# Sheet1.net
KiCad netlist of a schematic drawn in Altium Designer
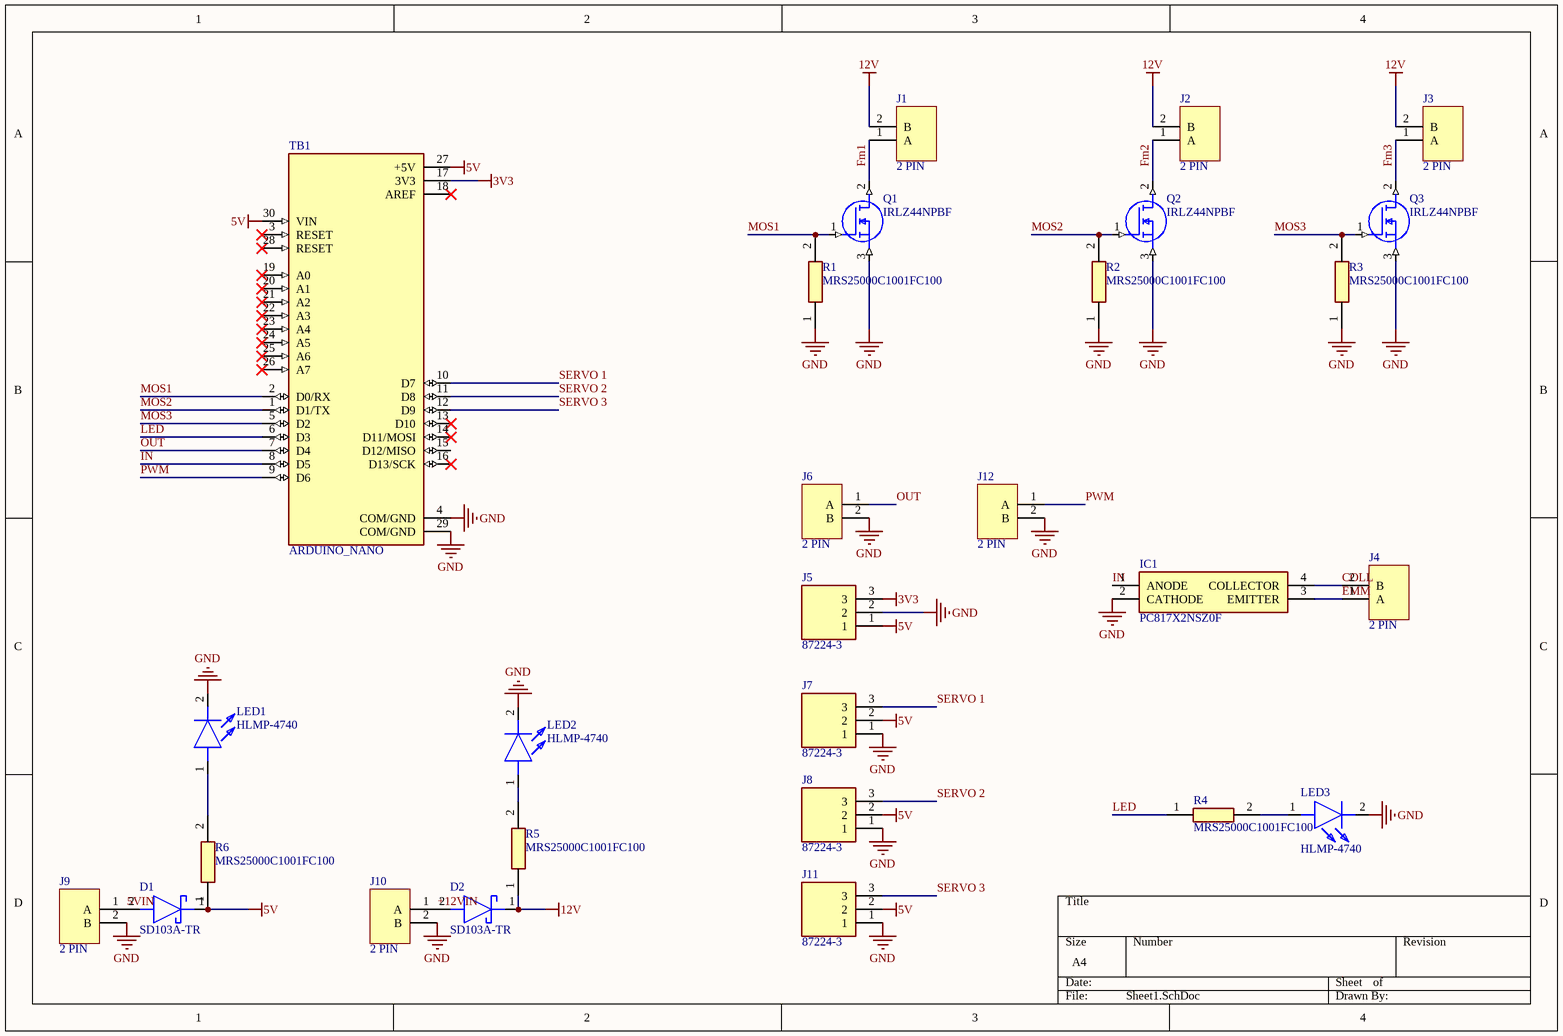
[diagram p0: Sheet1.SchDoc]

(export (version "E")
  (design (tool "Eeschema 10.0.6"))
  (components
    (comp (ref "D1")
      (value "SD103A-TR")
      (footprint "SamacSys:DIOAD950W60L350D150")
      (description "Schottky Diode")
      (fields (field (name "MOUSER PART NUMBER") "625-SD103A"))
      (libsource (lib "SamacSys") (part "SD103A-TR"))
    )
    (comp (ref "D2")
      (value "SD103A-TR")
      (footprint "SamacSys:DIOAD950W60L350D150")
      (description "Schottky Diode")
      (fields (field (name "MOUSER PART NUMBER") "625-SD103A"))
      (libsource (lib "SamacSys") (part "SD103A-TR"))
    )
    (comp (ref "IC1")
      (value "PC817X2NSZ0F")
      (footprint "SamacSys:DIP762W60P254L458H400Q4N")
      (description "Integrated Circuit")
      (libsource (lib "SamacSys") (part "PC817X2NSZ0F"))
    )
    (comp (ref "J1")
      (value "2 PIN")
      (footprint "Header 2_PIN")
      (libsource (lib "") (part "Connector_2Pin_1"))
    )
    (comp (ref "J2")
      (value "2 PIN")
      (footprint "Header 2_PIN")
      (libsource (lib "") (part "Connector_2Pin_1"))
    )
    (comp (ref "J3")
      (value "2 PIN")
      (footprint "Header 2_PIN")
      (libsource (lib "") (part "Connector_2Pin_1"))
    )
    (comp (ref "J4")
      (value "2 PIN")
      (footprint "Header 2_PIN")
      (libsource (lib "") (part "Connector_2Pin_1"))
    )
    (comp (ref "J5")
      (value "87224-3")
      (footprint "SamacSys:872243")
      (description "Connector")
      (fields (field (name "MOUSER PART NUMBER") "571-872243"))
      (libsource (lib "SamacSys") (part "87224-3"))
    )
    (comp (ref "J6")
      (value "2 PIN")
      (footprint "Header 2_PIN")
      (libsource (lib "Custom_Component") (part "Connector_2Pin"))
    )
    (comp (ref "J7")
      (value "87224-3")
      (footprint "SamacSys:872243")
      (description "Connector")
      (fields (field (name "MOUSER PART NUMBER") "571-872243"))
      (libsource (lib "SamacSys") (part "87224-3"))
    )
    (comp (ref "J8")
      (value "87224-3")
      (footprint "SamacSys:872243")
      (description "Connector")
      (fields (field (name "MOUSER PART NUMBER") "571-872243"))
      (libsource (lib "SamacSys") (part "87224-3"))
    )
    (comp (ref "J9")
      (value "2 PIN")
      (footprint "Header 2_PIN")
      (libsource (lib "Custom_Component") (part "Connector_2Pin"))
    )
    (comp (ref "J10")
      (value "2 PIN")
      (footprint "Header 2_PIN")
      (libsource (lib "Custom_Component") (part "Connector_2Pin"))
    )
    (comp (ref "J11")
      (value "87224-3")
      (footprint "SamacSys:872243")
      (description "Connector")
      (fields (field (name "MOUSER PART NUMBER") "571-872243"))
      (libsource (lib "SamacSys") (part "87224-3"))
    )
    (comp (ref "J12")
      (value "2 PIN")
      (footprint "Header 2_PIN")
      (libsource (lib "Custom_Component") (part "Connector_2Pin"))
    )
    (comp (ref "LED1")
      (value "HLMP-4740")
      (footprint "SamacSys:HLMP4740")
      (description "LED")
      (fields (field (name "MOUSER PART NUMBER") "630-HLMP-4740"))
      (libsource (lib "SamacSys") (part "HLMP-4740"))
    )
    (comp (ref "LED2")
      (value "HLMP-4740")
      (footprint "SamacSys:HLMP4740")
      (description "LED")
      (fields (field (name "MOUSER PART NUMBER") "630-HLMP-4740"))
      (libsource (lib "SamacSys") (part "HLMP-4740"))
    )
    (comp (ref "LED3")
      (value "HLMP-4740")
      (footprint "SamacSys:HLMP4740")
      (description "LED")
      (fields (field (name "MOUSER PART NUMBER") "630-HLMP-4740"))
      (libsource (lib "SamacSys") (part "HLMP-4740"))
    )
    (comp (ref "Q1")
      (value "IRLZ44NPBF")
      (footprint "SamacSys:TO254P469X1042X1967-3P")
      (description "MOSFET (N-Channel)")
      (fields (field (name "MOUSER PART NUMBER") "942-IRLZ44NPBF"))
      (libsource (lib "*") (part "IRLZ44NPBF"))
    )
    (comp (ref "Q2")
      (value "IRLZ44NPBF")
      (footprint "SamacSys:TO254P469X1042X1967-3P")
      (description "MOSFET (N-Channel)")
      (fields (field (name "MOUSER PART NUMBER") "942-IRLZ44NPBF"))
      (libsource (lib "*") (part "IRLZ44NPBF"))
    )
    (comp (ref "Q3")
      (value "IRLZ44NPBF")
      (footprint "SamacSys:TO254P469X1042X1967-3P")
      (description "MOSFET (N-Channel)")
      (fields (field (name "MOUSER PART NUMBER") "942-IRLZ44NPBF"))
      (libsource (lib "*") (part "IRLZ44NPBF"))
    )
    (comp (ref "R1")
      (value "MRS25000C1001FC100")
      (footprint "SamacSys:RESAD1650W60L650D250")
      (description "Resistor")
      (fields (field (name "MOUSER PART NUMBER") "594-MRS25000C1001FC1"))
      (libsource (lib "SamacSys") (part "MRS25000C1001FC100"))
    )
    (comp (ref "R2")
      (value "MRS25000C1001FC100")
      (footprint "SamacSys:RESAD1650W60L650D250")
      (description "Resistor")
      (fields (field (name "MOUSER PART NUMBER") "594-MRS25000C1001FC1"))
      (libsource (lib "SamacSys") (part "MRS25000C1001FC100"))
    )
    (comp (ref "R3")
      (value "MRS25000C1001FC100")
      (footprint "SamacSys:RESAD1650W60L650D250")
      (description "Resistor")
      (fields (field (name "MOUSER PART NUMBER") "594-MRS25000C1001FC1"))
      (libsource (lib "SamacSys") (part "MRS25000C1001FC100"))
    )
    (comp (ref "R4")
      (value "MRS25000C1001FC100")
      (footprint "SamacSys:RESAD1650W60L650D250")
      (description "Resistor")
      (fields (field (name "MOUSER PART NUMBER") "594-MRS25000C1001FC1"))
      (libsource (lib "") (part "MRS25000C1001FC100_1"))
    )
    (comp (ref "R5")
      (value "MRS25000C1001FC100")
      (footprint "SamacSys:RESAD1650W60L650D250")
      (description "Resistor")
      (fields (field (name "MOUSER PART NUMBER") "594-MRS25000C1001FC1"))
      (libsource (lib "SamacSys") (part "MRS25000C1001FC100"))
    )
    (comp (ref "R6")
      (value "MRS25000C1001FC100")
      (footprint "SamacSys:RESAD1650W60L650D250")
      (description "Resistor")
      (fields (field (name "MOUSER PART NUMBER") "594-MRS25000C1001FC1"))
      (libsource (lib "SamacSys") (part "MRS25000C1001FC100"))
    )
    (comp (ref "TB1")
      (value "ARDUINO_NANO")
      (footprint "SHIELD_ARDUINO_NANO")
      (description "Small, complete, and breadboard-friendly board based on the ATmega328 (Arduino Nano 3.x)")
      (fields (field (name "MP") "Arduino Nano") (field (name "MF") "Arduino"))
      (libsource (lib "ARDUINO_NANO") (part "ARDUINO_NANO"))
    )
  )
  (nets
    (net (code "1") (name "/+12VIN") (class "Default")
      (node (ref "D2") (pin "2") (pinfunction "A_2") (pintype "passive"))
      (node (ref "J10") (pin "1") (pinfunction "A_1") (pintype "passive"))
    )
    (net (code "2") (name "/5VIN") (class "Default")
      (node (ref "D1") (pin "2") (pinfunction "A_2") (pintype "passive"))
      (node (ref "J9") (pin "1") (pinfunction "A_1") (pintype "passive"))
    )
    (net (code "3") (name "/COLL") (class "Default")
      (node (ref "IC1") (pin "4") (pinfunction "COLLECTOR_4") (pintype "passive"))
      (node (ref "J4") (pin "2") (pinfunction "B_2") (pintype "passive"))
    )
    (net (code "4") (name "/EMM") (class "Default")
      (node (ref "IC1") (pin "3") (pinfunction "EMITTER_3") (pintype "passive"))
      (node (ref "J4") (pin "1") (pinfunction "A_1") (pintype "passive"))
    )
    (net (code "5") (name "/Fm1") (class "Default")
      (node (ref "J1") (pin "1") (pinfunction "A_1") (pintype "passive"))
      (node (ref "Q1") (pin "2") (pinfunction "D_2") (pintype "output"))
    )
    (net (code "6") (name "/Fm2") (class "Default")
      (node (ref "J2") (pin "1") (pinfunction "A_1") (pintype "passive"))
      (node (ref "Q2") (pin "2") (pinfunction "D_2") (pintype "output"))
    )
    (net (code "7") (name "/Fm3") (class "Default")
      (node (ref "J3") (pin "1") (pinfunction "A_1") (pintype "passive"))
      (node (ref "Q3") (pin "2") (pinfunction "D_2") (pintype "output"))
    )
    (net (code "8") (name "/IN") (class "Default")
      (node (ref "IC1") (pin "1") (pinfunction "ANODE_1") (pintype "passive"))
      (node (ref "TB1") (pin "8") (pinfunction "D5_8") (pintype "bidirectional"))
    )
    (net (code "9") (name "/LED") (class "Default")
      (node (ref "R4") (pin "1") (pinfunction "1_1") (pintype "passive"))
      (node (ref "TB1") (pin "6") (pinfunction "D3_6") (pintype "bidirectional"))
    )
    (net (code "10") (name "/MOS1") (class "Default")
      (node (ref "Q1") (pin "1") (pinfunction "G_1") (pintype "input"))
      (node (ref "R1") (pin "2") (pinfunction "2_2") (pintype "passive"))
      (node (ref "TB1") (pin "2") (pinfunction "D0/RX_2") (pintype "bidirectional"))
    )
    (net (code "11") (name "/MOS2") (class "Default")
      (node (ref "Q2") (pin "1") (pinfunction "G_1") (pintype "input"))
      (node (ref "R2") (pin "2") (pinfunction "2_2") (pintype "passive"))
      (node (ref "TB1") (pin "1") (pinfunction "D1/TX_1") (pintype "bidirectional"))
    )
    (net (code "12") (name "/MOS3") (class "Default")
      (node (ref "Q3") (pin "1") (pinfunction "G_1") (pintype "input"))
      (node (ref "R3") (pin "2") (pinfunction "2_2") (pintype "passive"))
      (node (ref "TB1") (pin "5") (pinfunction "D2_5") (pintype "bidirectional"))
    )
    (net (code "13") (name "/OUT") (class "Default")
      (node (ref "J6") (pin "1") (pinfunction "A_1") (pintype "passive"))
      (node (ref "TB1") (pin "7") (pinfunction "D4_7") (pintype "bidirectional"))
    )
    (net (code "14") (name "/PWM") (class "Default")
      (node (ref "J12") (pin "1") (pinfunction "A_1") (pintype "passive"))
      (node (ref "TB1") (pin "9") (pinfunction "D6_9") (pintype "bidirectional"))
    )
    (net (code "15") (name "/SERVO 1") (class "Default")
      (node (ref "J7") (pin "3") (pinfunction "3_3") (pintype "passive"))
      (node (ref "TB1") (pin "10") (pinfunction "D7_10") (pintype "bidirectional"))
    )
    (net (code "16") (name "/SERVO 2") (class "Default")
      (node (ref "J8") (pin "3") (pinfunction "3_3") (pintype "passive"))
      (node (ref "TB1") (pin "11") (pinfunction "D8_11") (pintype "bidirectional"))
    )
    (net (code "17") (name "/SERVO 3") (class "Default")
      (node (ref "J11") (pin "3") (pinfunction "3_3") (pintype "passive"))
      (node (ref "TB1") (pin "12") (pinfunction "D9_12") (pintype "bidirectional"))
    )
    (net (code "18") (name "3V3") (class "Default")
      (node (ref "J5") (pin "3") (pinfunction "3_3") (pintype "passive"))
      (node (ref "TB1") (pin "17") (pinfunction "3V3_17") (pintype "power_in"))
    )
    (net (code "19") (name "5V") (class "Default")
      (node (ref "D1") (pin "1") (pinfunction "K_1") (pintype "passive"))
      (node (ref "J11") (pin "2") (pinfunction "2_2") (pintype "passive"))
      (node (ref "J5") (pin "1") (pinfunction "1_1") (pintype "passive"))
      (node (ref "J7") (pin "2") (pinfunction "2_2") (pintype "passive"))
      (node (ref "J8") (pin "2") (pinfunction "2_2") (pintype "passive"))
      (node (ref "R6") (pin "1") (pinfunction "1_1") (pintype "passive"))
      (node (ref "TB1") (pin "27") (pinfunction "+5V_27") (pintype "power_in"))
      (node (ref "TB1") (pin "30") (pinfunction "VIN_30") (pintype "input"))
    )
    (net (code "20") (name "12V") (class "Default")
      (node (ref "D2") (pin "1") (pinfunction "K_1") (pintype "passive"))
      (node (ref "J1") (pin "2") (pinfunction "B_2") (pintype "passive"))
      (node (ref "J2") (pin "2") (pinfunction "B_2") (pintype "passive"))
      (node (ref "J3") (pin "2") (pinfunction "B_2") (pintype "passive"))
      (node (ref "R5") (pin "1") (pinfunction "1_1") (pintype "passive"))
    )
    (net (code "21") (name "GND") (class "Default")
      (node (ref "IC1") (pin "2") (pinfunction "CATHODE_2") (pintype "passive"))
      (node (ref "J10") (pin "2") (pinfunction "B_2") (pintype "passive"))
      (node (ref "J11") (pin "1") (pinfunction "1_1") (pintype "passive"))
      (node (ref "J12") (pin "2") (pinfunction "B_2") (pintype "passive"))
      (node (ref "J5") (pin "2") (pinfunction "2_2") (pintype "passive"))
      (node (ref "J6") (pin "2") (pinfunction "B_2") (pintype "passive"))
      (node (ref "J7") (pin "1") (pinfunction "1_1") (pintype "passive"))
      (node (ref "J8") (pin "1") (pinfunction "1_1") (pintype "passive"))
      (node (ref "J9") (pin "2") (pinfunction "B_2") (pintype "passive"))
      (node (ref "LED1") (pin "2") (pinfunction "K_2") (pintype "passive"))
      (node (ref "LED2") (pin "2") (pinfunction "K_2") (pintype "passive"))
      (node (ref "LED3") (pin "2") (pinfunction "K_2") (pintype "passive"))
      (node (ref "Q1") (pin "3") (pinfunction "S_3") (pintype "input"))
      (node (ref "Q2") (pin "3") (pinfunction "S_3") (pintype "input"))
      (node (ref "Q3") (pin "3") (pinfunction "S_3") (pintype "input"))
      (node (ref "R1") (pin "1") (pinfunction "1_1") (pintype "passive"))
      (node (ref "R2") (pin "1") (pinfunction "1_1") (pintype "passive"))
      (node (ref "R3") (pin "1") (pinfunction "1_1") (pintype "passive"))
      (node (ref "TB1") (pin "29") (pinfunction "COM/GND_29") (pintype "power_in"))
      (node (ref "TB1") (pin "4") (pinfunction "COM/GND_4") (pintype "power_in"))
    )
    (net (code "22") (name "Net-(LED1-A)") (class "Default")
      (node (ref "LED1") (pin "1") (pinfunction "A_1") (pintype "passive"))
      (node (ref "R6") (pin "2") (pinfunction "2_2") (pintype "passive"))
    )
    (net (code "23") (name "Net-(LED2-A)") (class "Default")
      (node (ref "LED2") (pin "1") (pinfunction "A_1") (pintype "passive"))
      (node (ref "R5") (pin "2") (pinfunction "2_2") (pintype "passive"))
    )
    (net (code "24") (name "Net-(LED3-A)") (class "Default")
      (node (ref "LED3") (pin "1") (pinfunction "A_1") (pintype "passive"))
      (node (ref "R4") (pin "2") (pinfunction "2_2") (pintype "passive"))
    )
    (net (code "25") (name "unconnected-(TB1-A0-Pad19)") (class "Default")
      (node (ref "TB1") (pin "19") (pinfunction "A0_19") (pintype "input+no_connect"))
    )
    (net (code "26") (name "unconnected-(TB1-A1-Pad20)") (class "Default")
      (node (ref "TB1") (pin "20") (pinfunction "A1_20") (pintype "input+no_connect"))
    )
    (net (code "27") (name "unconnected-(TB1-A2-Pad21)") (class "Default")
      (node (ref "TB1") (pin "21") (pinfunction "A2_21") (pintype "input+no_connect"))
    )
    (net (code "28") (name "unconnected-(TB1-A3-Pad22)") (class "Default")
      (node (ref "TB1") (pin "22") (pinfunction "A3_22") (pintype "input+no_connect"))
    )
    (net (code "29") (name "unconnected-(TB1-A4-Pad23)") (class "Default")
      (node (ref "TB1") (pin "23") (pinfunction "A4_23") (pintype "input+no_connect"))
    )
    (net (code "30") (name "unconnected-(TB1-A5-Pad24)") (class "Default")
      (node (ref "TB1") (pin "24") (pinfunction "A5_24") (pintype "input+no_connect"))
    )
    (net (code "31") (name "unconnected-(TB1-A6-Pad25)") (class "Default")
      (node (ref "TB1") (pin "25") (pinfunction "A6_25") (pintype "input+no_connect"))
    )
    (net (code "32") (name "unconnected-(TB1-A7-Pad26)") (class "Default")
      (node (ref "TB1") (pin "26") (pinfunction "A7_26") (pintype "input+no_connect"))
    )
    (net (code "33") (name "unconnected-(TB1-AREF-Pad18)") (class "Default")
      (node (ref "TB1") (pin "18") (pinfunction "AREF_18") (pintype "power_in+no_connect"))
    )
    (net (code "34") (name "unconnected-(TB1-D10-Pad13)") (class "Default")
      (node (ref "TB1") (pin "13") (pinfunction "D10_13") (pintype "bidirectional+no_connect"))
    )
    (net (code "35") (name "unconnected-(TB1-D11{slash}MOSI-Pad14)") (class "Default")
      (node (ref "TB1") (pin "14") (pinfunction "D11/MOSI_14") (pintype "bidirectional+no_connect"))
    )
    (net (code "36") (name "unconnected-(TB1-D12{slash}MISO-Pad15)") (class "Default")
      (node (ref "TB1") (pin "15") (pinfunction "D12/MISO_15") (pintype "bidirectional"))
    )
    (net (code "37") (name "unconnected-(TB1-D13{slash}SCK-Pad16)") (class "Default")
      (node (ref "TB1") (pin "16") (pinfunction "D13/SCK_16") (pintype "bidirectional+no_connect"))
    )
    (net (code "38") (name "unconnected-(TB1-RESET-Pad3)") (class "Default")
      (node (ref "TB1") (pin "3") (pinfunction "RESET_3") (pintype "input+no_connect"))
    )
    (net (code "39") (name "unconnected-(TB1-RESET-Pad28)") (class "Default")
      (node (ref "TB1") (pin "28") (pinfunction "RESET_28") (pintype "input+no_connect"))
    )
  )
)
